# External_WatchDogs.net
KiCad netlist of a schematic drawn in Altium Designer
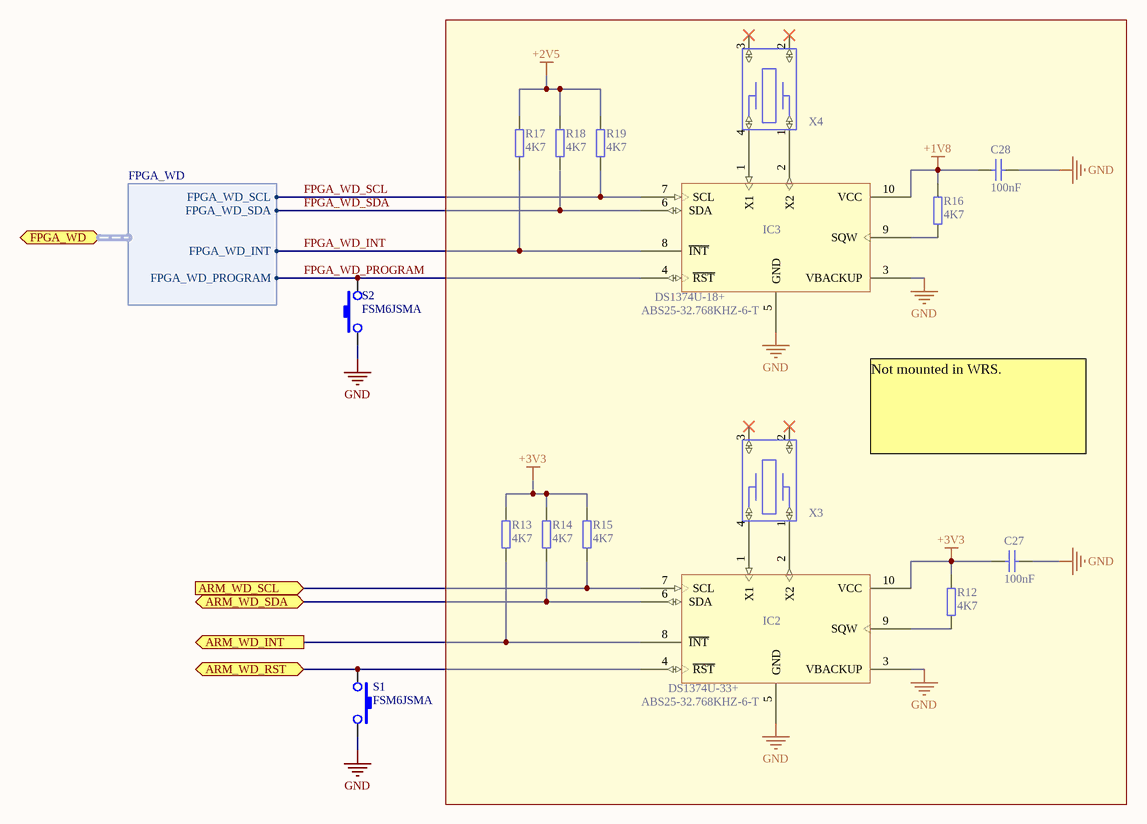
[diagram p0: External WatchDogs.SchDoc]

(export (version "E")
  (design (tool "Eeschema 10.0.6"))
  (components
    (comp (ref "C27")
      (value "100nF")
      (footprint "CC1005-0402")
      (description "Capacitor")
      (fields
        (field (name "TOLERANCE") "±10%")
        (field (name "VOLTAGE") "16V")
        (field (name "PUBLISHER") "Altium Limited")
      )
      (libsource (lib "wr_switch") (part "Cap"))
    )
    (comp (ref "C28")
      (value "100nF")
      (footprint "CC1005-0402")
      (description "Capacitor")
      (fields
        (field (name "TOLERANCE") "±10%")
        (field (name "VOLTAGE") "16V")
        (field (name "PUBLISHER") "Altium Limited")
      )
      (libsource (lib "wr_switch") (part "Cap"))
    )
    (comp (ref "IC2")
      (value "DS1374U-33+")
      (footprint "UMAX10")
      (description "I2C, 32 BIT BINARY COUNTER WATCHDOG RTC")
      (libsource (lib "wr_switch") (part "DS1374"))
    )
    (comp (ref "IC3")
      (value "DS1374U-18+")
      (footprint "UMAX10")
      (description "I2C, 32 BIT BINARY COUNTER WATCHDOG RTC")
      (libsource (lib "wr_switch") (part "DS1374"))
    )
    (comp (ref "R12")
      (value "4K7")
      (footprint "0402")
      (description "SMD Resistor")
      (fields (field (name "TOLERANCE") "±1%"))
      (libsource (lib "wr_switch") (part "RES_SMD"))
    )
    (comp (ref "R13")
      (value "4K7")
      (footprint "0402")
      (description "SMD Resistor")
      (fields (field (name "TOLERANCE") "±1%"))
      (libsource (lib "wr_switch") (part "RES_SMD"))
    )
    (comp (ref "R14")
      (value "4K7")
      (footprint "0402")
      (description "SMD Resistor")
      (fields (field (name "TOLERANCE") "±1%"))
      (libsource (lib "wr_switch") (part "RES_SMD"))
    )
    (comp (ref "R15")
      (value "4K7")
      (footprint "0402")
      (description "SMD Resistor")
      (fields (field (name "TOLERANCE") "±1%"))
      (libsource (lib "wr_switch") (part "RES_SMD"))
    )
    (comp (ref "R16")
      (value "4K7")
      (footprint "0402")
      (description "SMD Resistor")
      (fields (field (name "TOLERANCE") "±1%"))
      (libsource (lib "wr_switch") (part "RES_SMD"))
    )
    (comp (ref "R17")
      (value "4K7")
      (footprint "0402")
      (description "SMD Resistor")
      (fields (field (name "TOLERANCE") "±1%"))
      (libsource (lib "wr_switch") (part "RES_SMD"))
    )
    (comp (ref "R18")
      (value "4K7")
      (footprint "0402")
      (description "SMD Resistor")
      (fields (field (name "TOLERANCE") "±1%"))
      (libsource (lib "wr_switch") (part "RES_SMD"))
    )
    (comp (ref "R19")
      (value "4K7")
      (footprint "0402")
      (description "SMD Resistor")
      (fields (field (name "TOLERANCE") "±1%"))
      (libsource (lib "wr_switch") (part "RES_SMD"))
    )
    (comp (ref "S1")
      (value "FSM6JSMA")
      (footprint "SWITCH")
      (description "Push button")
      (fields (field (name "MANUFACTURER") "Tyco Electronics"))
      (libsource (lib "wr_switch") (part "SW-PB"))
    )
    (comp (ref "S2")
      (value "FSM6JSMA")
      (footprint "SWITCH")
      (description "Push button")
      (fields (field (name "MANUFACTURER") "Tyco Electronics"))
      (libsource (lib "wr_switch") (part "SW-PB"))
    )
    (comp (ref "X3")
      (value "ABS25-32.768KHZ-6-T")
      (footprint "ABS25")
      (description "Crystal 32.768 Hz 6,0pF SMD")
      (fields (field (name "MANF") "Abracon Corporation"))
      (libsource (lib "wr_switch") (part "ECSXTAL"))
    )
    (comp (ref "X4")
      (value "ABS25-32.768KHZ-6-T")
      (footprint "ABS25")
      (description "Crystal 32.768 Hz 6,0pF SMD")
      (fields (field (name "MANF") "Abracon Corporation"))
      (libsource (lib "wr_switch") (part "ECSXTAL"))
    )
  )
  (nets
    (net (code "2") (name "+1V8") (class "Default")
      (node (ref "C28") (pin "2") (pinfunction "2_2") (pintype "passive"))
      (node (ref "IC3") (pin "10") (pinfunction "VCC_10") (pintype "power_in"))
      (node (ref "R16") (pin "2") (pinfunction "2_2") (pintype "passive"))
    )
    (net (code "3") (name "+2V5") (class "Default")
      (node (ref "R17") (pin "2") (pinfunction "2_2") (pintype "passive"))
      (node (ref "R18") (pin "2") (pinfunction "2_2") (pintype "passive"))
      (node (ref "R19") (pin "2") (pinfunction "2_2") (pintype "passive"))
    )
    (net (code "4") (name "+3V3") (class "Default")
      (node (ref "C27") (pin "2") (pinfunction "2_2") (pintype "passive"))
      (node (ref "IC2") (pin "10") (pinfunction "VCC_10") (pintype "power_in"))
      (node (ref "R12") (pin "2") (pinfunction "2_2") (pintype "passive"))
      (node (ref "R13") (pin "2") (pinfunction "2_2") (pintype "passive"))
      (node (ref "R14") (pin "2") (pinfunction "2_2") (pintype "passive"))
      (node (ref "R15") (pin "2") (pinfunction "2_2") (pintype "passive"))
    )
    (net (code "5") (name "/ARM_WD_INT") (class "Default")
      (node (ref "IC2") (pin "8") (pinfunction "~{INT}_8") (pintype "open_collector"))
      (node (ref "R13") (pin "1") (pinfunction "1_1") (pintype "passive"))
    )
    (net (code "6") (name "/ARM_WD_RST") (class "Default")
      (node (ref "IC2") (pin "4") (pinfunction "~{RST}_4") (pintype "bidirectional"))
      (node (ref "S1") (pin "1") (pinfunction "1_1") (pintype "passive"))
    )
    (net (code "7") (name "/ARM_WD_SCL") (class "Default")
      (node (ref "IC2") (pin "7") (pinfunction "SCL_7") (pintype "input"))
      (node (ref "R15") (pin "1") (pinfunction "1_1") (pintype "passive"))
    )
    (net (code "8") (name "/ARM_WD_SDA") (class "Default")
      (node (ref "IC2") (pin "6") (pinfunction "SDA_6") (pintype "bidirectional"))
      (node (ref "R14") (pin "1") (pinfunction "1_1") (pintype "passive"))
    )
    (net (code "9") (name "/FPGA_WD_INT") (class "Default")
      (node (ref "IC3") (pin "8") (pinfunction "~{INT}_8") (pintype "open_collector"))
      (node (ref "R17") (pin "1") (pinfunction "1_1") (pintype "passive"))
    )
    (net (code "10") (name "/FPGA_WD_PROGRAM") (class "Default")
      (node (ref "IC3") (pin "4") (pinfunction "~{RST}_4") (pintype "bidirectional"))
      (node (ref "S2") (pin "2") (pinfunction "2_2") (pintype "passive"))
    )
    (net (code "11") (name "/FPGA_WD_SCL") (class "Default")
      (node (ref "IC3") (pin "7") (pinfunction "SCL_7") (pintype "input"))
      (node (ref "R19") (pin "1") (pinfunction "1_1") (pintype "passive"))
    )
    (net (code "12") (name "/FPGA_WD_SDA") (class "Default")
      (node (ref "IC3") (pin "6") (pinfunction "SDA_6") (pintype "bidirectional"))
      (node (ref "R18") (pin "1") (pinfunction "1_1") (pintype "passive"))
    )
    (net (code "14") (name "GND") (class "Default")
      (node (ref "C27") (pin "1") (pinfunction "1_1") (pintype "passive"))
      (node (ref "C28") (pin "1") (pinfunction "1_1") (pintype "passive"))
      (node (ref "IC2") (pin "3") (pinfunction "VBACKUP_3") (pintype "power_in"))
      (node (ref "IC2") (pin "5") (pinfunction "GND_5") (pintype "power_in"))
      (node (ref "IC3") (pin "3") (pinfunction "VBACKUP_3") (pintype "power_in"))
      (node (ref "IC3") (pin "5") (pinfunction "GND_5") (pintype "power_in"))
      (node (ref "S1") (pin "2") (pinfunction "2_2") (pintype "passive"))
      (node (ref "S2") (pin "1") (pinfunction "1_1") (pintype "passive"))
    )
    (net (code "15") (name "Net-(IC2-SQW)") (class "Default")
      (node (ref "IC2") (pin "9") (pinfunction "SQW_9") (pintype "open_collector"))
      (node (ref "R12") (pin "1") (pinfunction "1_1") (pintype "passive"))
    )
    (net (code "16") (name "Net-(IC2-X1)") (class "Default")
      (node (ref "IC2") (pin "1") (pinfunction "X1_1") (pintype "input"))
      (node (ref "X3") (pin "4") (pinfunction "P4_4") (pintype "bidirectional"))
    )
    (net (code "17") (name "Net-(IC2-X2)") (class "Default")
      (node (ref "IC2") (pin "2") (pinfunction "X2_2") (pintype "output"))
      (node (ref "X3") (pin "1") (pinfunction "P1_1") (pintype "bidirectional"))
    )
    (net (code "18") (name "Net-(IC3-SQW)") (class "Default")
      (node (ref "IC3") (pin "9") (pinfunction "SQW_9") (pintype "open_collector"))
      (node (ref "R16") (pin "1") (pinfunction "1_1") (pintype "passive"))
    )
    (net (code "19") (name "Net-(IC3-X1)") (class "Default")
      (node (ref "IC3") (pin "1") (pinfunction "X1_1") (pintype "input"))
      (node (ref "X4") (pin "4") (pinfunction "P4_4") (pintype "bidirectional"))
    )
    (net (code "20") (name "Net-(IC3-X2)") (class "Default")
      (node (ref "IC3") (pin "2") (pinfunction "X2_2") (pintype "output"))
      (node (ref "X4") (pin "1") (pinfunction "P1_1") (pintype "bidirectional"))
    )
    (net (code "21") (name "unconnected-(X3-P2-Pad2)") (class "Default")
      (node (ref "X3") (pin "2") (pinfunction "P2_2") (pintype "bidirectional+no_connect"))
    )
    (net (code "22") (name "unconnected-(X3-P3-Pad3)") (class "Default")
      (node (ref "X3") (pin "3") (pinfunction "P3_3") (pintype "bidirectional+no_connect"))
    )
    (net (code "23") (name "unconnected-(X4-P2-Pad2)") (class "Default")
      (node (ref "X4") (pin "2") (pinfunction "P2_2") (pintype "bidirectional+no_connect"))
    )
    (net (code "24") (name "unconnected-(X4-P3-Pad3)") (class "Default")
      (node (ref "X4") (pin "3") (pinfunction "P3_3") (pintype "bidirectional+no_connect"))
    )
  )
)
